# Relay_Latches.net
KiCad netlist of a schematic drawn in Altium Designer
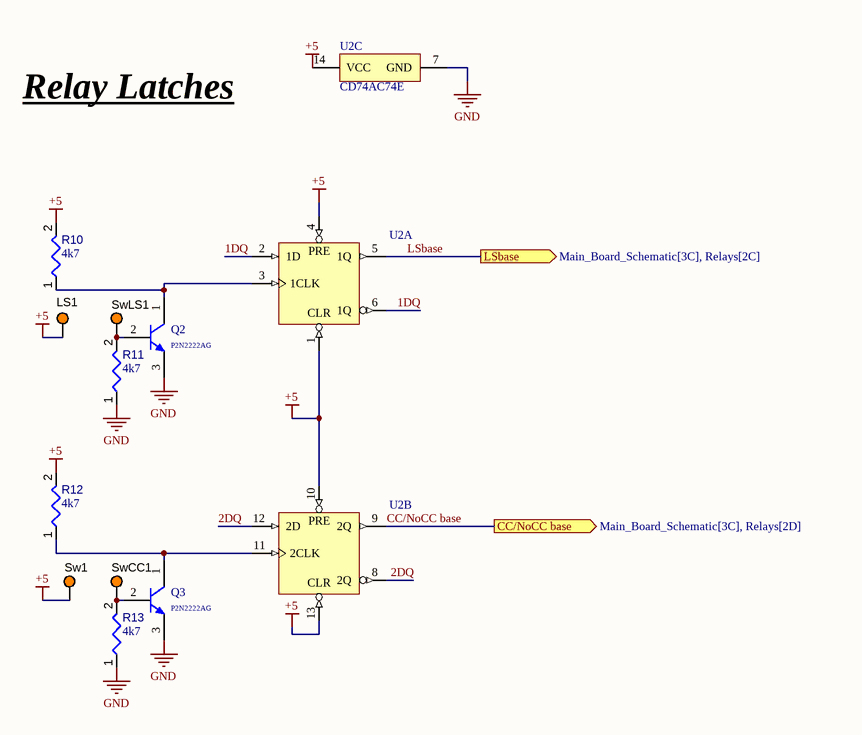
[diagram p0: Relay_Latches.SchDoc]

(export (version "E")
  (design (tool "Eeschema 10.0.6"))
  (components
    (comp (ref "LS1")
      (value "5003")
      (footprint "KSTN-5003")
      (description "Test Point, Orange, Height 4.6 mm, Tail Length 3 mm, 1-Pin THD, RoHS")
      (fields (field (name "MANUFACTURER") "Keystone"))
      (libsource (lib "Konstantinos Psarras") (part "TESTPOINT_ORANGE"))
    )
    (comp (ref "Q2")
      (value "P2N2222AG")
      (footprint "ONSC-TO-92-3-29-11")
      (description "Amplifier Transistor, NPN Silicon, 3-Pin TO-92, Pb-Free, Bulk Box")
      (fields (field (name "MANUFACTURER") "On Semiconductor"))
      (libsource (lib "Altium Content Vault") (part "ONSC-NPN-C1B2E3-3"))
    )
    (comp (ref "Q3")
      (value "P2N2222AG")
      (footprint "ONSC-TO-92-3-29-11")
      (description "Amplifier Transistor, NPN Silicon, 3-Pin TO-92, Pb-Free, Bulk Box")
      (fields (field (name "MANUFACTURER") "On Semiconductor"))
      (libsource (lib "Altium Content Vault") (part "ONSC-NPN-C1B2E3-3"))
    )
    (comp (ref "R10")
      (value "4k7")
      (footprint "RESA60-630X240")
      (description "Axial Resistor, 100 Ohm, +/- 1%, 0.25 W, -55 to 155 degC, 2-Pin THD, RoHS, Bulk")
      (fields (field (name "MANUFACTURER") "Yageo") (field (name "TOLERANCE") "1%"))
      (libsource (lib "Konstantinos Psarras") (part "RES-2"))
    )
    (comp (ref "R11")
      (value "4k7")
      (footprint "RESA60-630X240")
      (description "Axial Resistor, 100 Ohm, +/- 1%, 0.25 W, -55 to 155 degC, 2-Pin THD, RoHS, Bulk")
      (fields (field (name "MANUFACTURER") "Yageo") (field (name "TOLERANCE") "1%"))
      (libsource (lib "Konstantinos Psarras") (part "RES-2"))
    )
    (comp (ref "R12")
      (value "4k7")
      (footprint "RESA60-630X240")
      (description "Axial Resistor, 100 Ohm, +/- 1%, 0.25 W, -55 to 155 degC, 2-Pin THD, RoHS, Bulk")
      (fields (field (name "MANUFACTURER") "Yageo") (field (name "TOLERANCE") "1%"))
      (libsource (lib "Konstantinos Psarras") (part "RES-2"))
    )
    (comp (ref "R13")
      (value "4k7")
      (footprint "RESA60-630X240")
      (description "Axial Resistor, 100 Ohm, +/- 1%, 0.25 W, -55 to 155 degC, 2-Pin THD, RoHS, Bulk")
      (fields (field (name "MANUFACTURER") "Yageo") (field (name "TOLERANCE") "1%"))
      (libsource (lib "Konstantinos Psarras") (part "RES-2"))
    )
    (comp (ref "Sw1")
      (value "5003")
      (footprint "KSTN-5003")
      (description "Test Point, Orange, Height 4.6 mm, Tail Length 3 mm, 1-Pin THD, RoHS")
      (fields (field (name "MANUFACTURER") "Keystone"))
      (libsource (lib "Konstantinos Psarras") (part "TESTPOINT_ORANGE"))
    )
    (comp (ref "SwCC1")
      (value "5003")
      (footprint "KSTN-5003")
      (description "Test Point, Orange, Height 4.6 mm, Tail Length 3 mm, 1-Pin THD, RoHS")
      (fields (field (name "MANUFACTURER") "Keystone"))
      (libsource (lib "Konstantinos Psarras") (part "TESTPOINT_ORANGE"))
    )
    (comp (ref "SwLS1")
      (value "5003")
      (footprint "KSTN-5003")
      (description "Test Point, Orange, Height 4.6 mm, Tail Length 3 mm, 1-Pin THD, RoHS")
      (fields (field (name "MANUFACTURER") "Keystone"))
      (libsource (lib "Konstantinos Psarras") (part "TESTPOINT_ORANGE"))
    )
    (comp (ref "U2")
      (value "CD74AC74E")
      (footprint "N0014A")
      (description "Dual Positive-Edge-Triggered D-Type Flip-Flops with Set and Reset, N0014A, TUBE")
      (fields
        (field (name "GENERIC PART NUMBER") "CD74AC74")
        (field (name "MANUFACTURER") "Texas Instruments")
      )
      (libsource (lib "Altium Content Vault") (part "TI-CD_SNX4XXXX74X-14"))
    )
  )
  (nets
    (net (code "1") (name "+5") (class "Default")
      (node (ref "LS1") (pin "1") (pinfunction "1_1") (pintype "passive"))
      (node (ref "R10") (pin "2") (pinfunction "2_2") (pintype "passive"))
      (node (ref "R12") (pin "2") (pinfunction "2_2") (pintype "passive"))
      (node (ref "Sw1") (pin "1") (pinfunction "1_1") (pintype "passive"))
      (node (ref "U2") (pin "1") (pinfunction "1~{CLR}_1") (pintype "input"))
      (node (ref "U2") (pin "10") (pinfunction "2~{PRE}_10") (pintype "input"))
      (node (ref "U2") (pin "13") (pinfunction "2~{CLR}_13") (pintype "input"))
      (node (ref "U2") (pin "14") (pinfunction "VCC_14") (pintype "power_in"))
      (node (ref "U2") (pin "4") (pinfunction "1~{PRE}_4") (pintype "input"))
    )
    (net (code "2") (name "/1DQ") (class "Default")
      (node (ref "U2") (pin "2") (pinfunction "1D_2") (pintype "input"))
      (node (ref "U2") (pin "6") (pinfunction "1Q_6") (pintype "output"))
    )
    (net (code "3") (name "/2DQ") (class "Default")
      (node (ref "U2") (pin "12") (pinfunction "2D_12") (pintype "input"))
      (node (ref "U2") (pin "8") (pinfunction "2Q_8") (pintype "output"))
    )
    (net (code "4") (name "/CC{slash}NoCC base") (class "Default")
      (node (ref "U2") (pin "9") (pinfunction "2Q_9") (pintype "output"))
    )
    (net (code "5") (name "/LSbase") (class "Default")
      (node (ref "U2") (pin "5") (pinfunction "1Q_5") (pintype "output"))
    )
    (net (code "6") (name "GND") (class "Default")
      (node (ref "Q2") (pin "3") (pinfunction "E_3") (pintype "passive"))
      (node (ref "Q3") (pin "3") (pinfunction "E_3") (pintype "passive"))
      (node (ref "R11") (pin "1") (pinfunction "1_1") (pintype "passive"))
      (node (ref "R13") (pin "1") (pinfunction "1_1") (pintype "passive"))
      (node (ref "U2") (pin "7") (pinfunction "GND_7") (pintype "power_in"))
    )
    (net (code "7") (name "Net-(Q2-B)") (class "Default")
      (node (ref "Q2") (pin "2") (pinfunction "B_2") (pintype "passive"))
      (node (ref "R11") (pin "2") (pinfunction "2_2") (pintype "passive"))
      (node (ref "SwLS1") (pin "1") (pinfunction "1_1") (pintype "passive"))
    )
    (net (code "8") (name "Net-(Q2-C)") (class "Default")
      (node (ref "Q2") (pin "1") (pinfunction "C_1") (pintype "passive"))
      (node (ref "R10") (pin "1") (pinfunction "1_1") (pintype "passive"))
      (node (ref "U2") (pin "3") (pinfunction "1CLK_3") (pintype "input"))
    )
    (net (code "9") (name "Net-(Q3-B)") (class "Default")
      (node (ref "Q3") (pin "2") (pinfunction "B_2") (pintype "passive"))
      (node (ref "R13") (pin "2") (pinfunction "2_2") (pintype "passive"))
      (node (ref "SwCC1") (pin "1") (pinfunction "1_1") (pintype "passive"))
    )
    (net (code "10") (name "Net-(Q3-C)") (class "Default")
      (node (ref "Q3") (pin "1") (pinfunction "C_1") (pintype "passive"))
      (node (ref "R12") (pin "1") (pinfunction "1_1") (pintype "passive"))
      (node (ref "U2") (pin "11") (pinfunction "2CLK_11") (pintype "input"))
    )
  )
)
